# relay_module.net
KiCad netlist of a schematic drawn in Altium Designer
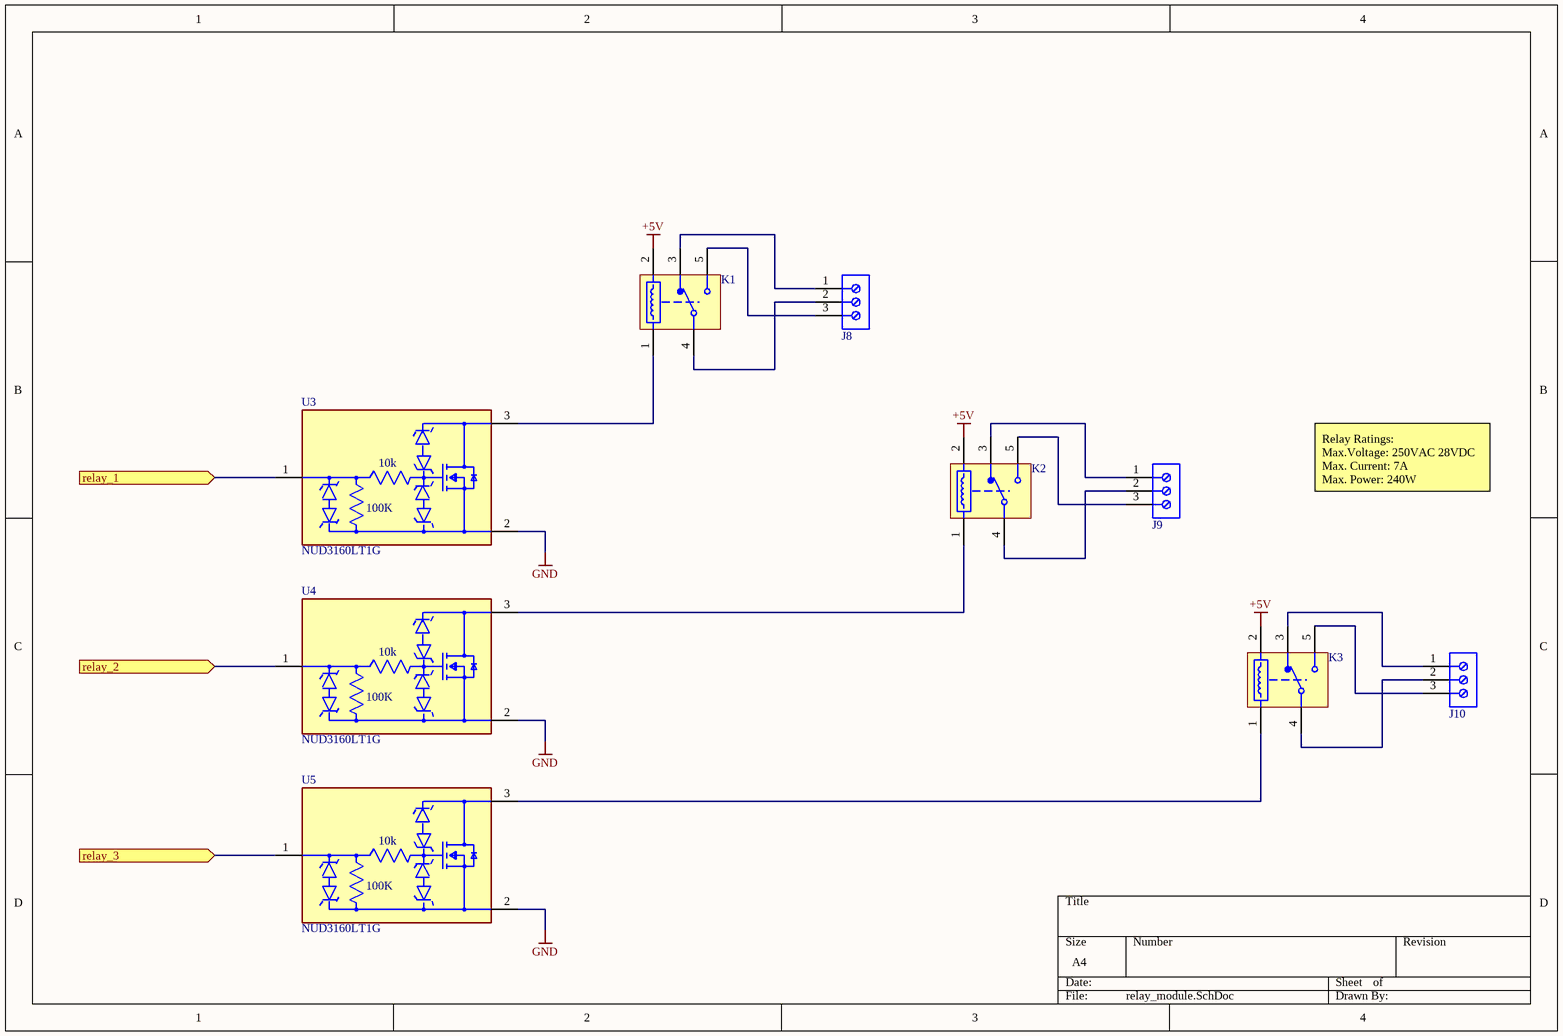
[diagram p0: relay_module.SchDoc]

(export (version "E")
  (design (tool "Eeschema 10.0.6"))
  (components
    (comp (ref "J8")
      (value "282836-3")
      (footprint "TE_282836-3")
      (description "Connector, Terminal Block; Wire Receptacle; 3 Pos.; 16-30 AWG; 0.197 in. CL; Sid")
      (fields (field (name "MANUFACTURER") "TE Connectivity") (field (name "VOLTAGE") "300V"))
      (libsource (lib "Schlib") (part "282836-3"))
    )
    (comp (ref "J9")
      (value "282836-3")
      (footprint "TE_282836-3")
      (description "Connector, Terminal Block; Wire Receptacle; 3 Pos.; 16-30 AWG; 0.197 in. CL; Sid")
      (fields (field (name "MANUFACTURER") "TE Connectivity") (field (name "VOLTAGE") "300V"))
      (libsource (lib "Schlib") (part "282836-3"))
    )
    (comp (ref "J10")
      (value "282836-3")
      (footprint "TE_282836-3")
      (description "Connector, Terminal Block; Wire Receptacle; 3 Pos.; 16-30 AWG; 0.197 in. CL; Sid")
      (fields (field (name "MANUFACTURER") "TE Connectivity") (field (name "VOLTAGE") "300V"))
      (libsource (lib "Schlib") (part "282836-3"))
    )
    (comp (ref "K1")
      (value "RELAY_SRD-05VDC-SL-C")
      (footprint "SRD-05-VDC-SL-C")
      (description "5VDC SPDT Relay")
      (libsource (lib "integrated_library") (part "RELAY_SRD-05VDC-SL-C"))
    )
    (comp (ref "K2")
      (value "RELAY_SRD-05VDC-SL-C")
      (footprint "SRD-05-VDC-SL-C")
      (description "5VDC SPDT Relay")
      (libsource (lib "integrated_library") (part "RELAY_SRD-05VDC-SL-C"))
    )
    (comp (ref "K3")
      (value "RELAY_SRD-05VDC-SL-C")
      (footprint "SRD-05-VDC-SL-C")
      (description "5VDC SPDT Relay")
      (libsource (lib "integrated_library") (part "RELAY_SRD-05VDC-SL-C"))
    )
    (comp (ref "U3")
      (value "NUD3160LT1G")
      (footprint "FP-318-08-MFG")
      (description "IC INDCT LOAD DRVR INDUST SOT23")
      (fields
        (field (name "OCTOPART") "https://octopart.com/nud3160lt1g-on+semiconductor-470723")
        (field (name "MANUFACTURER") "ON Semiconductor")
      )
      (libsource (lib "Altium Content Vault") (part "3565ae214b0a124fee97343a38643ca"))
    )
    (comp (ref "U4")
      (value "NUD3160LT1G")
      (footprint "FP-318-08-MFG")
      (description "IC INDCT LOAD DRVR INDUST SOT23")
      (fields
        (field (name "OCTOPART") "https://octopart.com/nud3160lt1g-on+semiconductor-470723")
        (field (name "MANUFACTURER") "ON Semiconductor")
      )
      (libsource (lib "Altium Content Vault") (part "3565ae214b0a124fee97343a38643ca"))
    )
    (comp (ref "U5")
      (value "NUD3160LT1G")
      (footprint "FP-318-08-MFG")
      (description "IC INDCT LOAD DRVR INDUST SOT23")
      (fields
        (field (name "OCTOPART") "https://octopart.com/nud3160lt1g-on+semiconductor-470723")
        (field (name "MANUFACTURER") "ON Semiconductor")
      )
      (libsource (lib "Altium Content Vault") (part "3565ae214b0a124fee97343a38643ca"))
    )
  )
  (nets
    (net (code "1") (name "+5V") (class "Default")
      (node (ref "K1") (pin "2") (pinfunction "2_2") (pintype "passive"))
      (node (ref "K2") (pin "2") (pinfunction "2_2") (pintype "passive"))
      (node (ref "K3") (pin "2") (pinfunction "2_2") (pintype "passive"))
    )
    (net (code "2") (name "/relay_1") (class "Default")
      (node (ref "U3") (pin "1") (pinfunction "Gate_1") (pintype "passive"))
    )
    (net (code "3") (name "/relay_2") (class "Default")
      (node (ref "U4") (pin "1") (pinfunction "Gate_1") (pintype "passive"))
    )
    (net (code "4") (name "/relay_3") (class "Default")
      (node (ref "U5") (pin "1") (pinfunction "Gate_1") (pintype "passive"))
    )
    (net (code "5") (name "GND") (class "Default")
      (node (ref "U3") (pin "2") (pinfunction "Source_2") (pintype "passive"))
      (node (ref "U4") (pin "2") (pinfunction "Source_2") (pintype "passive"))
      (node (ref "U5") (pin "2") (pinfunction "Source_2") (pintype "passive"))
    )
    (net (code "6") (name "Net-(K1-COM)") (class "Default")
      (node (ref "J8") (pin "2") (pinfunction "2_2") (pintype "passive"))
      (node (ref "K1") (pin "4") (pinfunction "COM_4") (pintype "passive"))
    )
    (net (code "7") (name "Net-(K1-NC)") (class "Default")
      (node (ref "J8") (pin "1") (pinfunction "1_1") (pintype "passive"))
      (node (ref "K1") (pin "3") (pinfunction "NC_3") (pintype "passive"))
    )
    (net (code "8") (name "Net-(K1-NO)") (class "Default")
      (node (ref "J8") (pin "3") (pinfunction "3_3") (pintype "passive"))
      (node (ref "K1") (pin "5") (pinfunction "NO_5") (pintype "passive"))
    )
    (net (code "9") (name "Net-(K2-COM)") (class "Default")
      (node (ref "J9") (pin "2") (pinfunction "2_2") (pintype "passive"))
      (node (ref "K2") (pin "4") (pinfunction "COM_4") (pintype "passive"))
    )
    (net (code "10") (name "Net-(K2-NC)") (class "Default")
      (node (ref "J9") (pin "1") (pinfunction "1_1") (pintype "passive"))
      (node (ref "K2") (pin "3") (pinfunction "NC_3") (pintype "passive"))
    )
    (net (code "11") (name "Net-(K2-NO)") (class "Default")
      (node (ref "J9") (pin "3") (pinfunction "3_3") (pintype "passive"))
      (node (ref "K2") (pin "5") (pinfunction "NO_5") (pintype "passive"))
    )
    (net (code "12") (name "Net-(K3-COM)") (class "Default")
      (node (ref "J10") (pin "2") (pinfunction "2_2") (pintype "passive"))
      (node (ref "K3") (pin "4") (pinfunction "COM_4") (pintype "passive"))
    )
    (net (code "13") (name "Net-(K3-NC)") (class "Default")
      (node (ref "J10") (pin "1") (pinfunction "1_1") (pintype "passive"))
      (node (ref "K3") (pin "3") (pinfunction "NC_3") (pintype "passive"))
    )
    (net (code "14") (name "Net-(K3-NO)") (class "Default")
      (node (ref "J10") (pin "3") (pinfunction "3_3") (pintype "passive"))
      (node (ref "K3") (pin "5") (pinfunction "NO_5") (pintype "passive"))
    )
    (net (code "15") (name "Net-(U3-Drain)") (class "Default")
      (node (ref "K1") (pin "1") (pinfunction "1_1") (pintype "passive"))
      (node (ref "U3") (pin "3") (pinfunction "Drain_3") (pintype "passive"))
    )
    (net (code "16") (name "Net-(U4-Drain)") (class "Default")
      (node (ref "K2") (pin "1") (pinfunction "1_1") (pintype "passive"))
      (node (ref "U4") (pin "3") (pinfunction "Drain_3") (pintype "passive"))
    )
    (net (code "17") (name "Net-(U5-Drain)") (class "Default")
      (node (ref "K3") (pin "1") (pinfunction "1_1") (pintype "passive"))
      (node (ref "U5") (pin "3") (pinfunction "Drain_3") (pintype "passive"))
    )
  )
)
